# codec_controller.net
KiCad netlist of a schematic drawn in EAGLE
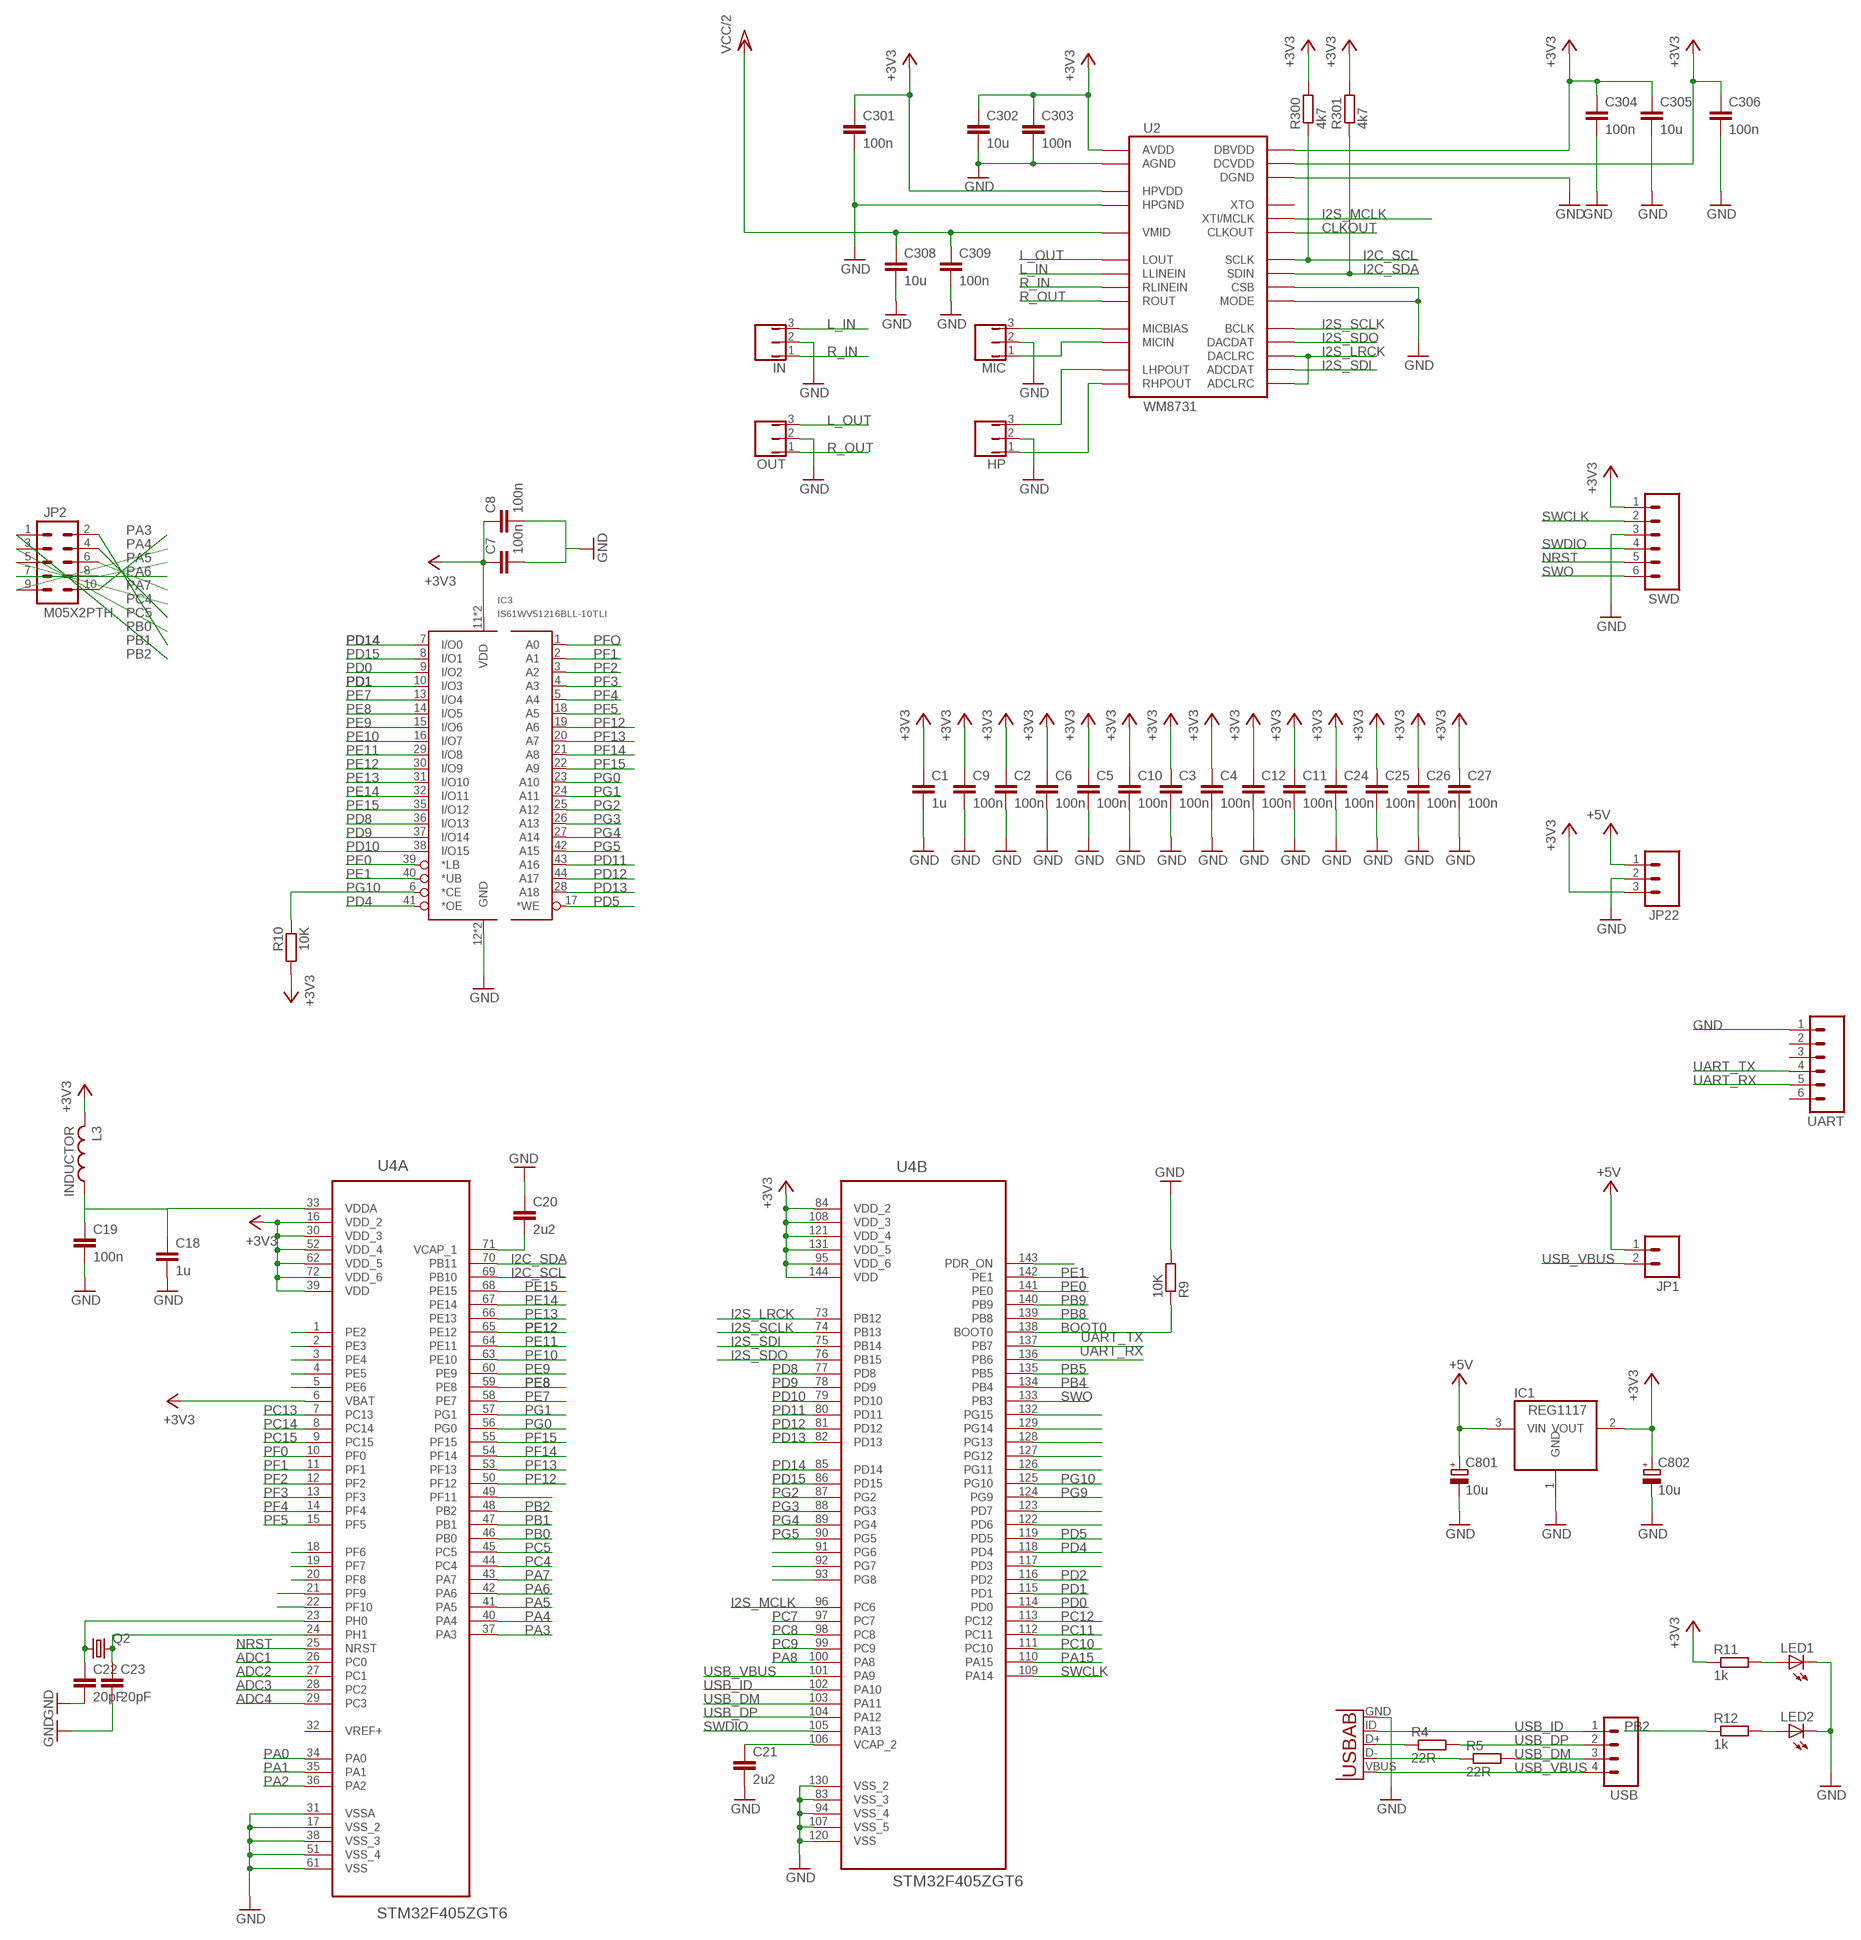
[diagram p0: schematic, sheet 1]

(export (version "E")
  (design (tool "Eeschema 10.0.6"))
  (components
    (comp (ref "C1")
      (value "1u")
      (footprint "eagle-import:C0603")
      (libsource (lib "eagle-import") (part "C-EUC0603"))
    )
    (comp (ref "C2")
      (value "100n")
      (footprint "eagle-import:C0603")
      (libsource (lib "eagle-import") (part "C-EUC0603"))
    )
    (comp (ref "C3")
      (value "100n")
      (footprint "eagle-import:C0603")
      (libsource (lib "eagle-import") (part "C-EUC0603"))
    )
    (comp (ref "C4")
      (value "100n")
      (footprint "eagle-import:C0603")
      (libsource (lib "eagle-import") (part "C-EUC0603"))
    )
    (comp (ref "C5")
      (value "100n")
      (footprint "eagle-import:C0603")
      (libsource (lib "eagle-import") (part "C-EUC0603"))
    )
    (comp (ref "C6")
      (value "100n")
      (footprint "eagle-import:C0603")
      (libsource (lib "eagle-import") (part "C-EUC0603"))
    )
    (comp (ref "C7")
      (value "100n")
      (footprint "eagle-import:C0603")
      (libsource (lib "eagle-import") (part "C-EUC0603"))
    )
    (comp (ref "C8")
      (value "100n")
      (footprint "eagle-import:C0603")
      (libsource (lib "eagle-import") (part "C-EUC0603"))
    )
    (comp (ref "C9")
      (value "100n")
      (footprint "eagle-import:C0603")
      (libsource (lib "eagle-import") (part "C-EUC0603"))
    )
    (comp (ref "C10")
      (value "100n")
      (footprint "eagle-import:C0603")
      (libsource (lib "eagle-import") (part "C-EUC0603"))
    )
    (comp (ref "C11")
      (value "100n")
      (footprint "eagle-import:C0603")
      (libsource (lib "eagle-import") (part "C-EUC0603"))
    )
    (comp (ref "C12")
      (value "100n")
      (footprint "eagle-import:C0603")
      (libsource (lib "eagle-import") (part "C-EUC0603"))
    )
    (comp (ref "C18")
      (value "1u")
      (footprint "eagle-import:C0603")
      (libsource (lib "eagle-import") (part "C-EUC0603"))
    )
    (comp (ref "C19")
      (value "100n")
      (footprint "eagle-import:C0603")
      (libsource (lib "eagle-import") (part "C-EUC0603"))
    )
    (comp (ref "C20")
      (value "2u2")
      (footprint "eagle-import:C0603")
      (libsource (lib "eagle-import") (part "C-EUC0603"))
    )
    (comp (ref "C21")
      (value "2u2")
      (footprint "eagle-import:C0603")
      (libsource (lib "eagle-import") (part "C-EUC0603"))
    )
    (comp (ref "C22")
      (value "20pF")
      (footprint "eagle-import:C0603")
      (libsource (lib "eagle-import") (part "C-EUC0603"))
    )
    (comp (ref "C23")
      (value "20pF")
      (footprint "eagle-import:C0603")
      (libsource (lib "eagle-import") (part "C-EUC0603"))
    )
    (comp (ref "C24")
      (value "100n")
      (footprint "eagle-import:C0603")
      (libsource (lib "eagle-import") (part "C-EUC0603"))
    )
    (comp (ref "C25")
      (value "100n")
      (footprint "eagle-import:C0603")
      (libsource (lib "eagle-import") (part "C-EUC0603"))
    )
    (comp (ref "C26")
      (value "100n")
      (footprint "eagle-import:C0603")
      (libsource (lib "eagle-import") (part "C-EUC0603"))
    )
    (comp (ref "C27")
      (value "100n")
      (footprint "eagle-import:C0603")
      (libsource (lib "eagle-import") (part "C-EUC0603"))
    )
    (comp (ref "C301")
      (value "100n")
      (footprint "eagle-import:C0603")
      (libsource (lib "eagle-import") (part "C-EUC0603"))
    )
    (comp (ref "C302")
      (value "10u")
      (footprint "eagle-import:C1206")
      (libsource (lib "eagle-import") (part "C-EUC1206"))
    )
    (comp (ref "C303")
      (value "100n")
      (footprint "eagle-import:C0603")
      (libsource (lib "eagle-import") (part "C-EUC0603"))
    )
    (comp (ref "C304")
      (value "100n")
      (footprint "eagle-import:C0603")
      (libsource (lib "eagle-import") (part "C-EUC0603"))
    )
    (comp (ref "C305")
      (value "10u")
      (footprint "eagle-import:C1206")
      (libsource (lib "eagle-import") (part "C-EUC1206"))
    )
    (comp (ref "C306")
      (value "100n")
      (footprint "eagle-import:C0603")
      (libsource (lib "eagle-import") (part "C-EUC0603"))
    )
    (comp (ref "C308")
      (value "10u")
      (footprint "eagle-import:C1206")
      (libsource (lib "eagle-import") (part "C-EUC1206"))
    )
    (comp (ref "C309")
      (value "100n")
      (footprint "eagle-import:C0603")
      (libsource (lib "eagle-import") (part "C-EUC0603"))
    )
    (comp (ref "C801")
      (value "10u")
      (footprint "eagle-import:PANASONIC_A")
      (libsource (lib "eagle-import") (part "CPOL-EUA"))
    )
    (comp (ref "C802")
      (value "10u")
      (footprint "eagle-import:PANASONIC_A")
      (libsource (lib "eagle-import") (part "CPOL-EUA"))
    )
    (comp (ref "HP")
      (value "JMP/3P/SIP")
      (footprint "eagle-import:JMP_3P_SIP")
      (libsource (lib "eagle-import") (part "JMP/3P/SIP"))
    )
    (comp (ref "IC1")
      (value "REG1117")
      (footprint "eagle-import:SOT223")
      (libsource (lib "eagle-import") (part "REG1117"))
    )
    (comp (ref "IC3")
      (value "IS61WV51216BLL-10TLI")
      (footprint "eagle-import:TSOP44-II")
      (libsource (lib "eagle-import") (part "IS61WV51216BLL-10TLI"))
    )
    (comp (ref "IN")
      (value "JMP/3P/SIP")
      (footprint "eagle-import:JMP_3P_SIP")
      (libsource (lib "eagle-import") (part "JMP/3P/SIP"))
    )
    (comp (ref "JP1")
      (value "M02PTH")
      (footprint "eagle-import:1X02")
      (libsource (lib "eagle-import") (part "M02PTH"))
    )
    (comp (ref "JP2")
      (value "M05X2PTH")
      (footprint "eagle-import:AVR_ICSP")
      (libsource (lib "eagle-import") (part "M05X2PTH"))
    )
    (comp (ref "JP22")
      (value "M03PTH")
      (footprint "eagle-import:1X03")
      (libsource (lib "eagle-import") (part "M03PTH"))
    )
    (comp (ref "L3")
      (value "INDUCTOR")
      (footprint "eagle-import:0603")
      (libsource (lib "eagle-import") (part "INDUCTOR"))
    )
    (comp (ref "LED1")
      (value "LED1206")
      (footprint "eagle-import:LED-1206")
      (libsource (lib "eagle-import") (part "LED1206"))
    )
    (comp (ref "LED2")
      (value "LED1206")
      (footprint "eagle-import:LED-1206")
      (libsource (lib "eagle-import") (part "LED1206"))
    )
    (comp (ref "MIC")
      (value "JMP/3P/SIP")
      (footprint "eagle-import:JMP_3P_SIP")
      (libsource (lib "eagle-import") (part "JMP/3P/SIP"))
    )
    (comp (ref "OUT")
      (value "JMP/3P/SIP")
      (footprint "eagle-import:JMP_3P_SIP")
      (libsource (lib "eagle-import") (part "JMP/3P/SIP"))
    )
    (comp (ref "Q2")
      (value "CRYSTALHC49UP")
      (footprint "eagle-import:HC49UP")
      (libsource (lib "eagle-import") (part "CRYSTALHC49UP"))
    )
    (comp (ref "R4")
      (value "22R")
      (footprint "eagle-import:R0603")
      (libsource (lib "eagle-import") (part "R-EU_R0603"))
    )
    (comp (ref "R5")
      (value "22R")
      (footprint "eagle-import:R0603")
      (libsource (lib "eagle-import") (part "R-EU_R0603"))
    )
    (comp (ref "R9")
      (value "10K")
      (footprint "eagle-import:R0603")
      (libsource (lib "eagle-import") (part "R-EU_R0603"))
    )
    (comp (ref "R10")
      (value "10K")
      (footprint "eagle-import:R0603")
      (libsource (lib "eagle-import") (part "R-EU_R0603"))
    )
    (comp (ref "R11")
      (value "1k")
      (footprint "eagle-import:R0603")
      (libsource (lib "eagle-import") (part "R-EU_R0603"))
    )
    (comp (ref "R12")
      (value "1k")
      (footprint "eagle-import:R0603")
      (libsource (lib "eagle-import") (part "R-EU_R0603"))
    )
    (comp (ref "R300")
      (value "4k7")
      (footprint "eagle-import:R0603")
      (libsource (lib "eagle-import") (part "R-EU_R0603"))
    )
    (comp (ref "R301")
      (value "4k7")
      (footprint "eagle-import:R0603")
      (libsource (lib "eagle-import") (part "R-EU_R0603"))
    )
    (comp (ref "SWD")
      (value "M06SIP")
      (footprint "eagle-import:1X06")
      (libsource (lib "eagle-import") (part "M06SIP"))
    )
    (comp (ref "U2")
      (value "WM8731")
      (footprint "eagle-import:28-SSOP")
      (libsource (lib "eagle-import") (part "WM8731"))
    )
    (comp (ref "U3")
      (value "USB-AB")
      (footprint "eagle-import:USB-AB-MICRO-SMD")
      (libsource (lib "eagle-import") (part "USB-AB"))
    )
    (comp (ref "U4")
      (value "STM32F405ZGT6")
      (footprint "eagle-import:QFP50P2200X2200X160-144N")
      (libsource (lib "eagle-import") (part "STM32F405ZGT6"))
    )
    (comp (ref "UART")
      (value "M06SIP")
      (footprint "eagle-import:1X06")
      (libsource (lib "eagle-import") (part "M06SIP"))
    )
    (comp (ref "USB")
      (value "M04PTH")
      (footprint "eagle-import:1X04")
      (libsource (lib "eagle-import") (part "M04PTH"))
    )
  )
  (nets
    (net (code "1") (name "+3V3") (class "Default")
      (node (ref "C1") (pin "1") (pinfunction "1_1") (pintype "passive"))
      (node (ref "C10") (pin "1") (pinfunction "1_1") (pintype "passive"))
      (node (ref "C11") (pin "1") (pinfunction "1_1") (pintype "passive"))
      (node (ref "C12") (pin "1") (pinfunction "1_1") (pintype "passive"))
      (node (ref "C2") (pin "1") (pinfunction "1_1") (pintype "passive"))
      (node (ref "C24") (pin "1") (pinfunction "1_1") (pintype "passive"))
      (node (ref "C25") (pin "1") (pinfunction "1_1") (pintype "passive"))
      (node (ref "C26") (pin "1") (pinfunction "1_1") (pintype "passive"))
      (node (ref "C27") (pin "1") (pinfunction "1_1") (pintype "passive"))
      (node (ref "C3") (pin "1") (pinfunction "1_1") (pintype "passive"))
      (node (ref "C301") (pin "1") (pinfunction "1_1") (pintype "passive"))
      (node (ref "C302") (pin "1") (pinfunction "1_1") (pintype "passive"))
      (node (ref "C303") (pin "1") (pinfunction "1_1") (pintype "passive"))
      (node (ref "C304") (pin "1") (pinfunction "1_1") (pintype "passive"))
      (node (ref "C305") (pin "1") (pinfunction "1_1") (pintype "passive"))
      (node (ref "C306") (pin "1") (pinfunction "1_1") (pintype "passive"))
      (node (ref "C4") (pin "1") (pinfunction "1_1") (pintype "passive"))
      (node (ref "C5") (pin "1") (pinfunction "1_1") (pintype "passive"))
      (node (ref "C6") (pin "1") (pinfunction "1_1") (pintype "passive"))
      (node (ref "C7") (pin "1") (pinfunction "1_1") (pintype "passive"))
      (node (ref "C8") (pin "1") (pinfunction "1_1") (pintype "passive"))
      (node (ref "C802") (pin "+") (pinfunction "+_+") (pintype "passive"))
      (node (ref "C9") (pin "1") (pinfunction "1_1") (pintype "passive"))
      (node (ref "IC1") (pin "2") (pinfunction "VOUT_2") (pintype "output"))
      (node (ref "IC3") (pin "11") (pinfunction "VDD_11") (pintype "power_in"))
      (node (ref "IC3") (pin "33") (pinfunction "VDD_33") (pintype "power_in"))
      (node (ref "JP22") (pin "3") (pinfunction "3_3") (pintype "passive"))
      (node (ref "L3") (pin "2") (pinfunction "2_2") (pintype "passive"))
      (node (ref "R10") (pin "2") (pinfunction "2_2") (pintype "passive"))
      (node (ref "R11") (pin "1") (pinfunction "1_1") (pintype "passive"))
      (node (ref "R300") (pin "2") (pinfunction "2_2") (pintype "passive"))
      (node (ref "R301") (pin "2") (pinfunction "2_2") (pintype "passive"))
      (node (ref "SWD") (pin "1") (pinfunction "1_1") (pintype "passive"))
      (node (ref "U2") (pin "P$1") (pinfunction "DBVDD_P$1") (pintype "power_in"))
      (node (ref "U2") (pin "P$14") (pinfunction "AVDD_P$14") (pintype "power_in"))
      (node (ref "U2") (pin "P$27") (pinfunction "DCVDD_P$27") (pintype "power_in"))
      (node (ref "U2") (pin "P$8") (pinfunction "HPVDD_P$8") (pintype "power_in"))
      (node (ref "U4") (pin "108") (pinfunction "VDD_3_108") (pintype "power_in"))
      (node (ref "U4") (pin "121") (pinfunction "VDD_4_121") (pintype "power_in"))
      (node (ref "U4") (pin "131") (pinfunction "VDD_5_131") (pintype "power_in"))
      (node (ref "U4") (pin "144") (pinfunction "VDD_144") (pintype "power_in"))
      (node (ref "U4") (pin "16") (pinfunction "VDD_2_16") (pintype "power_in"))
      (node (ref "U4") (pin "30") (pinfunction "VDD_3_30") (pintype "power_in"))
      (node (ref "U4") (pin "39") (pinfunction "VDD_39") (pintype "power_in"))
      (node (ref "U4") (pin "52") (pinfunction "VDD_4_52") (pintype "power_in"))
      (node (ref "U4") (pin "6") (pinfunction "VBAT_6") (pintype "passive"))
      (node (ref "U4") (pin "62") (pinfunction "VDD_5_62") (pintype "power_in"))
      (node (ref "U4") (pin "72") (pinfunction "VDD_6_72") (pintype "power_in"))
      (node (ref "U4") (pin "84") (pinfunction "VDD_2_84") (pintype "power_in"))
      (node (ref "U4") (pin "95") (pinfunction "VDD_6_95") (pintype "power_in"))
    )
    (net (code "2") (name "+5V") (class "Default")
      (node (ref "C801") (pin "+") (pinfunction "+_+") (pintype "passive"))
      (node (ref "IC1") (pin "3") (pinfunction "VIN_3") (pintype "input"))
      (node (ref "JP1") (pin "1") (pinfunction "1_1") (pintype "passive"))
      (node (ref "JP22") (pin "1") (pinfunction "1_1") (pintype "passive"))
    )
    (net (code "3") (name "/ADC1") (class "Default")
      (node (ref "U4") (pin "26") (pinfunction "PC0_26") (pintype "bidirectional"))
    )
    (net (code "4") (name "/ADC2") (class "Default")
      (node (ref "U4") (pin "27") (pinfunction "PC1_27") (pintype "bidirectional"))
    )
    (net (code "5") (name "/ADC3") (class "Default")
      (node (ref "U4") (pin "28") (pinfunction "PC2_28") (pintype "bidirectional"))
    )
    (net (code "6") (name "/ADC4") (class "Default")
      (node (ref "U4") (pin "29") (pinfunction "PC3_29") (pintype "bidirectional"))
    )
    (net (code "7") (name "/BOOT0") (class "Default")
      (node (ref "R9") (pin "1") (pinfunction "1_1") (pintype "passive"))
      (node (ref "U4") (pin "138") (pinfunction "BOOT0_138") (pintype "passive"))
    )
    (net (code "8") (name "/CLKOUT") (class "Default")
      (node (ref "U2") (pin "P$2") (pinfunction "CLKOUT_P$2") (pintype "output"))
    )
    (net (code "9") (name "/I2C_SCL") (class "Default")
      (node (ref "R300") (pin "1") (pinfunction "1_1") (pintype "passive"))
      (node (ref "U2") (pin "P$24") (pinfunction "SCLK_P$24") (pintype "input"))
      (node (ref "U4") (pin "69") (pinfunction "PB10_69") (pintype "bidirectional"))
    )
    (net (code "10") (name "/I2C_SDA") (class "Default")
      (node (ref "R301") (pin "1") (pinfunction "1_1") (pintype "passive"))
      (node (ref "U2") (pin "P$23") (pinfunction "SDIN_P$23") (pintype "bidirectional"))
      (node (ref "U4") (pin "70") (pinfunction "PB11_70") (pintype "bidirectional"))
    )
    (net (code "11") (name "/I2S_LRCK") (class "Default")
      (node (ref "U2") (pin "P$5") (pinfunction "DACLRC_P$5") (pintype "bidirectional"))
      (node (ref "U2") (pin "P$7") (pinfunction "ADCLRC_P$7") (pintype "bidirectional"))
      (node (ref "U4") (pin "73") (pinfunction "PB12_73") (pintype "bidirectional"))
    )
    (net (code "12") (name "/I2S_MCLK") (class "Default")
      (node (ref "U2") (pin "P$25") (pinfunction "XTI/MCLK_P$25") (pintype "input"))
      (node (ref "U4") (pin "96") (pinfunction "PC6_96") (pintype "bidirectional"))
    )
    (net (code "13") (name "/I2S_SCLK") (class "Default")
      (node (ref "U2") (pin "P$3") (pinfunction "BCLK_P$3") (pintype "bidirectional"))
      (node (ref "U4") (pin "74") (pinfunction "PB13_74") (pintype "bidirectional"))
    )
    (net (code "14") (name "/I2S_SDI") (class "Default")
      (node (ref "U2") (pin "P$6") (pinfunction "ADCDAT_P$6") (pintype "output"))
      (node (ref "U4") (pin "75") (pinfunction "PB14_75") (pintype "bidirectional"))
    )
    (net (code "15") (name "/I2S_SDO") (class "Default")
      (node (ref "U2") (pin "P$4") (pinfunction "DACDAT_P$4") (pintype "input"))
      (node (ref "U4") (pin "76") (pinfunction "PB15_76") (pintype "bidirectional"))
    )
    (net (code "16") (name "/L_IN") (class "Default")
      (node (ref "IN") (pin "3") (pinfunction "3_3") (pintype "passive"))
      (node (ref "U2") (pin "P$20") (pinfunction "LLINEIN_P$20") (pintype "input"))
    )
    (net (code "17") (name "/L_OUT") (class "Default")
      (node (ref "OUT") (pin "3") (pinfunction "3_3") (pintype "passive"))
      (node (ref "U2") (pin "P$12") (pinfunction "LOUT_P$12") (pintype "output"))
    )
    (net (code "18") (name "/NRST") (class "Default")
      (node (ref "SWD") (pin "5") (pinfunction "5_5") (pintype "passive"))
      (node (ref "U4") (pin "25") (pinfunction "NRST_25") (pintype "passive"))
    )
    (net (code "19") (name "/PA0") (class "Default")
      (node (ref "U4") (pin "34") (pinfunction "PA0_34") (pintype "bidirectional"))
    )
    (net (code "20") (name "/PA1") (class "Default")
      (node (ref "U4") (pin "35") (pinfunction "PA1_35") (pintype "bidirectional"))
    )
    (net (code "21") (name "/PA2") (class "Default")
      (node (ref "U4") (pin "36") (pinfunction "PA2_36") (pintype "bidirectional"))
    )
    (net (code "22") (name "/PA3") (class "Default")
      (node (ref "JP2") (pin "10") (pinfunction "10_10") (pintype "passive"))
      (node (ref "U4") (pin "37") (pinfunction "PA3_37") (pintype "bidirectional"))
    )
    (net (code "23") (name "/PA4") (class "Default")
      (node (ref "JP2") (pin "9") (pinfunction "9_9") (pintype "passive"))
      (node (ref "U4") (pin "40") (pinfunction "PA4_40") (pintype "bidirectional"))
    )
    (net (code "24") (name "/PA5") (class "Default")
      (node (ref "JP2") (pin "8") (pinfunction "8_8") (pintype "passive"))
      (node (ref "U4") (pin "41") (pinfunction "PA5_41") (pintype "bidirectional"))
    )
    (net (code "25") (name "/PA6") (class "Default")
      (node (ref "JP2") (pin "7") (pinfunction "7_7") (pintype "passive"))
      (node (ref "U4") (pin "42") (pinfunction "PA6_42") (pintype "bidirectional"))
    )
    (net (code "26") (name "/PA7") (class "Default")
      (node (ref "JP2") (pin "6") (pinfunction "6_6") (pintype "passive"))
      (node (ref "U4") (pin "43") (pinfunction "PA7_43") (pintype "bidirectional"))
    )
    (net (code "27") (name "/PA8") (class "Default")
      (node (ref "U4") (pin "100") (pinfunction "PA8_100") (pintype "bidirectional"))
    )
    (net (code "28") (name "/PA15") (class "Default")
      (node (ref "U4") (pin "110") (pinfunction "PA15_110") (pintype "bidirectional"))
    )
    (net (code "29") (name "/PB0") (class "Default")
      (node (ref "JP2") (pin "3") (pinfunction "3_3") (pintype "passive"))
      (node (ref "U4") (pin "46") (pinfunction "PB0_46") (pintype "bidirectional"))
    )
    (net (code "30") (name "/PB1") (class "Default")
      (node (ref "JP2") (pin "2") (pinfunction "2_2") (pintype "passive"))
      (node (ref "U4") (pin "47") (pinfunction "PB1_47") (pintype "bidirectional"))
    )
    (net (code "31") (name "/PB2") (class "Default")
      (node (ref "JP2") (pin "1") (pinfunction "1_1") (pintype "passive"))
      (node (ref "R12") (pin "1") (pinfunction "1_1") (pintype "passive"))
      (node (ref "U4") (pin "48") (pinfunction "PB2_48") (pintype "bidirectional"))
    )
    (net (code "32") (name "/PB4") (class "Default")
      (node (ref "U4") (pin "134") (pinfunction "PB4_134") (pintype "bidirectional"))
    )
    (net (code "33") (name "/PB5") (class "Default")
      (node (ref "U4") (pin "135") (pinfunction "PB5_135") (pintype "bidirectional"))
    )
    (net (code "34") (name "/PB8") (class "Default")
      (node (ref "U4") (pin "139") (pinfunction "PB8_139") (pintype "bidirectional"))
    )
    (net (code "35") (name "/PB9") (class "Default")
      (node (ref "U4") (pin "140") (pinfunction "PB9_140") (pintype "bidirectional"))
    )
    (net (code "36") (name "/PC4") (class "Default")
      (node (ref "JP2") (pin "5") (pinfunction "5_5") (pintype "passive"))
      (node (ref "U4") (pin "44") (pinfunction "PC4_44") (pintype "bidirectional"))
    )
    (net (code "37") (name "/PC5") (class "Default")
      (node (ref "JP2") (pin "4") (pinfunction "4_4") (pintype "passive"))
      (node (ref "U4") (pin "45") (pinfunction "PC5_45") (pintype "bidirectional"))
    )
    (net (code "38") (name "/PC7") (class "Default")
      (node (ref "U4") (pin "97") (pinfunction "PC7_97") (pintype "bidirectional"))
    )
    (net (code "39") (name "/PC8") (class "Default")
      (node (ref "U4") (pin "98") (pinfunction "PC8_98") (pintype "bidirectional"))
    )
    (net (code "40") (name "/PC9") (class "Default")
      (node (ref "U4") (pin "99") (pinfunction "PC9_99") (pintype "bidirectional"))
    )
    (net (code "41") (name "/PC10") (class "Default")
      (node (ref "U4") (pin "111") (pinfunction "PC10_111") (pintype "bidirectional"))
    )
    (net (code "42") (name "/PC11") (class "Default")
      (node (ref "U4") (pin "112") (pinfunction "PC11_112") (pintype "bidirectional"))
    )
    (net (code "43") (name "/PC12") (class "Default")
      (node (ref "U4") (pin "113") (pinfunction "PC12_113") (pintype "bidirectional"))
    )
    (net (code "44") (name "/PC13") (class "Default")
      (node (ref "U4") (pin "7") (pinfunction "PC13_7") (pintype "bidirectional"))
    )
    (net (code "45") (name "/PC14") (class "Default")
      (node (ref "U4") (pin "8") (pinfunction "PC14_8") (pintype "bidirectional"))
    )
    (net (code "46") (name "/PC15") (class "Default")
      (node (ref "U4") (pin "9") (pinfunction "PC15_9") (pintype "bidirectional"))
    )
    (net (code "47") (name "/PD0") (class "Default")
      (node (ref "IC3") (pin "9") (pinfunction "I/O2_9") (pintype "bidirectional"))
      (node (ref "U4") (pin "114") (pinfunction "PD0_114") (pintype "bidirectional"))
    )
    (net (code "48") (name "/PD1") (class "Default")
      (node (ref "IC3") (pin "10") (pinfunction "I/O3_10") (pintype "bidirectional"))
      (node (ref "U4") (pin "115") (pinfunction "PD1_115") (pintype "bidirectional"))
    )
    (net (code "49") (name "/PD2") (class "Default")
      (node (ref "U4") (pin "116") (pinfunction "PD2_116") (pintype "bidirectional"))
    )
    (net (code "50") (name "/PD4") (class "Default")
      (node (ref "IC3") (pin "41") (pinfunction "*OE_41") (pintype "bidirectional"))
      (node (ref "U4") (pin "118") (pinfunction "PD4_118") (pintype "bidirectional"))
    )
    (net (code "51") (name "/PD5") (class "Default")
      (node (ref "IC3") (pin "17") (pinfunction "*WE_17") (pintype "bidirectional"))
      (node (ref "U4") (pin "119") (pinfunction "PD5_119") (pintype "bidirectional"))
    )
    (net (code "52") (name "/PD8") (class "Default")
      (node (ref "IC3") (pin "36") (pinfunction "I/O13_36") (pintype "bidirectional"))
      (node (ref "U4") (pin "77") (pinfunction "PD8_77") (pintype "bidirectional"))
    )
    (net (code "53") (name "/PD9") (class "Default")
      (node (ref "IC3") (pin "37") (pinfunction "I/O14_37") (pintype "bidirectional"))
      (node (ref "U4") (pin "78") (pinfunction "PD9_78") (pintype "bidirectional"))
    )
    (net (code "54") (name "/PD10") (class "Default")
      (node (ref "IC3") (pin "38") (pinfunction "I/O15_38") (pintype "bidirectional"))
      (node (ref "U4") (pin "79") (pinfunction "PD10_79") (pintype "bidirectional"))
    )
    (net (code "55") (name "/PD11") (class "Default")
      (node (ref "IC3") (pin "43") (pinfunction "A16_43") (pintype "input"))
      (node (ref "U4") (pin "80") (pinfunction "PD11_80") (pintype "bidirectional"))
    )
    (net (code "56") (name "/PD12") (class "Default")
      (node (ref "IC3") (pin "44") (pinfunction "A17_44") (pintype "input"))
      (node (ref "U4") (pin "81") (pinfunction "PD12_81") (pintype "bidirectional"))
    )
    (net (code "57") (name "/PD13") (class "Default")
      (node (ref "IC3") (pin "28") (pinfunction "A18_28") (pintype "input"))
      (node (ref "U4") (pin "82") (pinfunction "PD13_82") (pintype "bidirectional"))
    )
    (net (code "58") (name "/PD14") (class "Default")
      (node (ref "IC3") (pin "7") (pinfunction "I/O0_7") (pintype "bidirectional"))
      (node (ref "U4") (pin "85") (pinfunction "PD14_85") (pintype "bidirectional"))
    )
    (net (code "59") (name "/PD15") (class "Default")
      (node (ref "IC3") (pin "8") (pinfunction "I/O1_8") (pintype "bidirectional"))
      (node (ref "U4") (pin "86") (pinfunction "PD15_86") (pintype "bidirectional"))
    )
    (net (code "60") (name "/PE0") (class "Default")
      (node (ref "IC3") (pin "39") (pinfunction "*LB_39") (pintype "bidirectional"))
      (node (ref "U4") (pin "141") (pinfunction "PE0_141") (pintype "bidirectional"))
    )
    (net (code "61") (name "/PE1") (class "Default")
      (node (ref "IC3") (pin "40") (pinfunction "*UB_40") (pintype "bidirectional"))
      (node (ref "U4") (pin "142") (pinfunction "PE1_142") (pintype "bidirectional"))
    )
    (net (code "62") (name "/PE7") (class "Default")
      (node (ref "IC3") (pin "13") (pinfunction "I/O4_13") (pintype "bidirectional"))
      (node (ref "U4") (pin "58") (pinfunction "PE7_58") (pintype "bidirectional"))
    )
    (net (code "63") (name "/PE8") (class "Default")
      (node (ref "IC3") (pin "14") (pinfunction "I/O5_14") (pintype "bidirectional"))
      (node (ref "U4") (pin "59") (pinfunction "PE8_59") (pintype "bidirectional"))
    )
    (net (code "64") (name "/PE9") (class "Default")
      (node (ref "IC3") (pin "15") (pinfunction "I/O6_15") (pintype "bidirectional"))
      (node (ref "U4") (pin "60") (pinfunction "PE9_60") (pintype "bidirectional"))
    )
    (net (code "65") (name "/PE10") (class "Default")
      (node (ref "IC3") (pin "16") (pinfunction "I/O7_16") (pintype "bidirectional"))
      (node (ref "U4") (pin "63") (pinfunction "PE10_63") (pintype "bidirectional"))
    )
    (net (code "66") (name "/PE11") (class "Default")
      (node (ref "IC3") (pin "29") (pinfunction "I/O8_29") (pintype "bidirectional"))
      (node (ref "U4") (pin "64") (pinfunction "PE11_64") (pintype "bidirectional"))
    )
    (net (code "67") (name "/PE12") (class "Default")
      (node (ref "IC3") (pin "30") (pinfunction "I/O9_30") (pintype "bidirectional"))
      (node (ref "U4") (pin "65") (pinfunction "PE12_65") (pintype "bidirectional"))
    )
    (net (code "68") (name "/PE13") (class "Default")
      (node (ref "IC3") (pin "31") (pinfunction "I/O10_31") (pintype "bidirectional"))
      (node (ref "U4") (pin "66") (pinfunction "PE13_66") (pintype "bidirectional"))
    )
    (net (code "69") (name "/PE14") (class "Default")
      (node (ref "IC3") (pin "32") (pinfunction "I/O11_32") (pintype "bidirectional"))
      (node (ref "U4") (pin "67") (pinfunction "PE14_67") (pintype "bidirectional"))
    )
    (net (code "70") (name "/PE15") (class "Default")
      (node (ref "IC3") (pin "35") (pinfunction "I/O12_35") (pintype "bidirectional"))
      (node (ref "U4") (pin "68") (pinfunction "PE15_68") (pintype "bidirectional"))
    )
    (net (code "71") (name "/PF0") (class "Default")
      (node (ref "U4") (pin "10") (pinfunction "PF0_10") (pintype "bidirectional"))
    )
    (net (code "72") (name "/PF1") (class "Default")
      (node (ref "IC3") (pin "2") (pinfunction "A1_2") (pintype "input"))
      (node (ref "U4") (pin "11") (pinfunction "PF1_11") (pintype "bidirectional"))
    )
    (net (code "73") (name "/PF2") (class "Default")
      (node (ref "IC3") (pin "3") (pinfunction "A2_3") (pintype "input"))
      (node (ref "U4") (pin "12") (pinfunction "PF2_12") (pintype "bidirectional"))
    )
    (net (code "74") (name "/PF3") (class "Default")
      (node (ref "IC3") (pin "4") (pinfunction "A3_4") (pintype "input"))
      (node (ref "U4") (pin "13") (pinfunction "PF3_13") (pintype "bidirectional"))
    )
    (net (code "75") (name "/PF4") (class "Default")
      (node (ref "IC3") (pin "5") (pinfunction "A4_5") (pintype "input"))
      (node (ref "U4") (pin "14") (pinfunction "PF4_14") (pintype "bidirectional"))
    )
    (net (code "76") (name "/PF5") (class "Default")
      (node (ref "IC3") (pin "18") (pinfunction "A5_18") (pintype "input"))
      (node (ref "U4") (pin "15") (pinfunction "PF5_15") (pintype "bidirectional"))
    )
    (net (code "77") (name "/PF12") (class "Default")
      (node (ref "IC3") (pin "19") (pinfunction "A6_19") (pintype "input"))
      (node (ref "U4") (pin "50") (pinfunction "PF12_50") (pintype "bidirectional"))
    )
    (net (code "78") (name "/PF13") (class "Default")
      (node (ref "IC3") (pin "20") (pinfunction "A7_20") (pintype "input"))
      (node (ref "U4") (pin "53") (pinfunction "PF13_53") (pintype "bidirectional"))
    )
    (net (code "79") (name "/PF14") (class "Default")
      (node (ref "IC3") (pin "21") (pinfunction "A8_21") (pintype "input"))
      (node (ref "U4") (pin "54") (pinfunction "PF14_54") (pintype "bidirectional"))
    )
    (net (code "80") (name "/PF15") (class "Default")
      (node (ref "IC3") (pin "22") (pinfunction "A9_22") (pintype "input"))
      (node (ref "U4") (pin "55") (pinfunction "PF15_55") (pintype "bidirectional"))
    )
    (net (code "81") (name "/PFO") (class "Default")
      (node (ref "IC3") (pin "1") (pinfunction "A0_1") (pintype "input"))
    )
    (net (code "82") (name "/PG0") (class "Default")
      (node (ref "IC3") (pin "23") (pinfunction "A10_23") (pintype "input"))
      (node (ref "U4") (pin "56") (pinfunction "PG0_56") (pintype "bidirectional"))
    )
    (net (code "83") (name "/PG1") (class "Default")
      (node (ref "IC3") (pin "24") (pinfunction "A11_24") (pintype "input"))
      (node (ref "U4") (pin "57") (pinfunction "PG1_57") (pintype "bidirectional"))
    )
    (net (code "84") (name "/PG2") (class "Default")
      (node (ref "IC3") (pin "25") (pinfunction "A12_25") (pintype "input"))
      (node (ref "U4") (pin "87") (pinfunction "PG2_87") (pintype "bidirectional"))
    )
    (net (code "85") (name "/PG3") (class "Default")
      (node (ref "IC3") (pin "26") (pinfunction "A13_26") (pintype "input"))
      (node (ref "U4") (pin "88") (pinfunction "PG3_88") (pintype "bidirectional"))
    )
    (net (code "86") (name "/PG4") (class "Default")
      (node (ref "IC3") (pin "27") (pinfunction "A14_27") (pintype "input"))
      (node (ref "U4") (pin "89") (pinfunction "PG4_89") (pintype "bidirectional"))
    )
    (net (code "87") (name "/PG5") (class "Default")
      (node (ref "IC3") (pin "42") (pinfunction "A15_42") (pintype "input"))
      (node (ref "U4") (pin "90") (pinfunction "PG5_90") (pintype "bidirectional"))
    )
    (net (code "88") (name "/PG9") (class "Default")
      (node (ref "U4") (pin "124") (pinfunction "PG9_124") (pintype "bidirectional"))
    )
    (net (code "89") (name "/PG10") (class "Default")
      (node (ref "IC3") (pin "6") (pinfunction "*CE_6") (pintype "bidirectional"))
      (node (ref "R10") (pin "1") (pinfunction "1_1") (pintype "passive"))
      (node (ref "U4") (pin "125") (pinfunction "PG10_125") (pintype "bidirectional"))
    )
    (net (code "90") (name "/R_IN") (class "Default")
      (node (ref "IN") (pin "1") (pinfunction "1_1") (pintype "passive"))
      (node (ref "U2") (pin "P$19") (pinfunction "RLINEIN_P$19") (pintype "input"))
    )
    (net (code "91") (name "/R_OUT") (class "Default")
      (node (ref "OUT") (pin "1") (pinfunction "1_1") (pintype "passive"))
      (node (ref "U2") (pin "P$13") (pinfunction "ROUT_P$13") (pintype "output"))
    )
    (net (code "92") (name "/SWCLK") (class "Default")
      (node (ref "SWD") (pin "2") (pinfunction "2_2") (pintype "passive"))
      (node (ref "U4") (pin "109") (pinfunction "PA14_109") (pintype "bidirectional"))
    )
    (net (code "93") (name "/SWDIO") (class "Default")
      (node (ref "SWD") (pin "4") (pinfunction "4_4") (pintype "passive"))
      (node (ref "U4") (pin "105") (pinfunction "PA13_105") (pintype "bidirectional"))
    )
    (net (code "94") (name "/SWO") (class "Default")
      (node (ref "SWD") (pin "6") (pinfunction "6_6") (pintype "passive"))
      (node (ref "U4") (pin "133") (pinfunction "PB3_133") (pintype "bidirectional"))
    )
    (net (code "95") (name "/UART_RX") (class "Default")
      (node (ref "U4") (pin "136") (pinfunction "PB6_136") (pintype "bidirectional"))
      (node (ref "UART") (pin "5") (pinfunction "5_5") (pintype "passive"))
    )
    (net (code "96") (name "/UART_TX") (class "Default")
      (node (ref "U4") (pin "137") (pinfunction "PB7_137") (pintype "bidirectional"))
      (node (ref "UART") (pin "4") (pinfunction "4_4") (pintype "passive"))
    )
    (net (code "97") (name "/USB_DM") (class "Default")
      (node (ref "R5") (pin "2") (pinfunction "2_2") (pintype "passive"))
      (node (ref "U4") (pin "103") (pinfunction "PA11_103") (pintype "bidirectional"))
      (node (ref "USB") (pin "3") (pinfunction "3_3") (pintype "passive"))
    )
    (net (code "98") (name "/USB_DP") (class "Default")
      (node (ref "R4") (pin "2") (pinfunction "2_2") (pintype "passive"))
      (node (ref "U4") (pin "104") (pinfunction "PA12_104") (pintype "bidirectional"))
      (node (ref "USB") (pin "2") (pinfunction "2_2") (pintype "passive"))
    )
    (net (code "99") (name "/USB_ID") (class "Default")
      (node (ref "U3") (pin "ID") (pinfunction "USBID_ID") (pintype "bidirectional"))
      (node (ref "U4") (pin "102") (pinfunction "PA10_102") (pintype "bidirectional"))
      (node (ref "USB") (pin "1") (pinfunction "1_1") (pintype "passive"))
    )
    (net (code "100") (name "/USB_VBUS") (class "Default")
      (node (ref "JP1") (pin "2") (pinfunction "2_2") (pintype "passive"))
      (node (ref "U3") (pin "VBUS") (pinfunction "VBUS_VBUS") (pintype "bidirectional"))
      (node (ref "U4") (pin "101") (pinfunction "PA9_101") (pintype "bidirectional"))
      (node (ref "USB") (pin "4") (pinfunction "4_4") (pintype "passive"))
    )
    (net (code "101") (name "GND") (class "Default")
      (node (ref "C1") (pin "2") (pinfunction "2_2") (pintype "passive"))
      (node (ref "C10") (pin "2") (pinfunction "2_2") (pintype "passive"))
      (node (ref "C11") (pin "2") (pinfunction "2_2") (pintype "passive"))
      (node (ref "C12") (pin "2") (pinfunction "2_2") (pintype "passive"))
      (node (ref "C18") (pin "2") (pinfunction "2_2") (pintype "passive"))
      (node (ref "C19") (pin "2") (pinfunction "2_2") (pintype "passive"))
      (node (ref "C2") (pin "2") (pinfunction "2_2") (pintype "passive"))
      (node (ref "C20") (pin "1") (pinfunction "1_1") (pintype "passive"))
      (node (ref "C21") (pin "2") (pinfunction "2_2") (pintype "passive"))
      (node (ref "C22") (pin "2") (pinfunction "2_2") (pintype "passive"))
      (node (ref "C23") (pin "2") (pinfunction "2_2") (pintype "passive"))
      (node (ref "C24") (pin "2") (pinfunction "2_2") (pintype "passive"))
      (node (ref "C25") (pin "2") (pinfunction "2_2") (pintype "passive"))
      (node (ref "C26") (pin "2") (pinfunction "2_2") (pintype "passive"))
      (node (ref "C27") (pin "2") (pinfunction "2_2") (pintype "passive"))
      (node (ref "C3") (pin "2") (pinfunction "2_2") (pintype "passive"))
      (node (ref "C301") (pin "2") (pinfunction "2_2") (pintype "passive"))
      (node (ref "C302") (pin "2") (pinfunction "2_2") (pintype "passive"))
      (node (ref "C303") (pin "2") (pinfunction "2_2") (pintype "passive"))
      (node (ref "C304") (pin "2") (pinfunction "2_2") (pintype "passive"))
      (node (ref "C305") (pin "2") (pinfunction "2_2") (pintype "passive"))
      (node (ref "C306") (pin "2") (pinfunction "2_2") (pintype "passive"))
      (node (ref "C308") (pin "2") (pinfunction "2_2") (pintype "passive"))
      (node (ref "C309") (pin "2") (pinfunction "2_2") (pintype "passive"))
      (node (ref "C4") (pin "2") (pinfunction "2_2") (pintype "passive"))
      (node (ref "C5") (pin "2") (pinfunction "2_2") (pintype "passive"))
      (node (ref "C6") (pin "2") (pinfunction "2_2") (pintype "passive"))
      (node (ref "C7") (pin "2") (pinfunction "2_2") (pintype "passive"))
      (node (ref "C8") (pin "2") (pinfunction "2_2") (pintype "passive"))
      (node (ref "C801") (pin "-") (pinfunction "-_-") (pintype "passive"))
      (node (ref "C802") (pin "-") (pinfunction "-_-") (pintype "passive"))
      (node (ref "C9") (pin "2") (pinfunction "2_2") (pintype "passive"))
      (node (ref "HP") (pin "2") (pinfunction "2_2") (pintype "passive"))
      (node (ref "IC1") (pin "1") (pinfunction "GND_1") (pintype "power_in"))
      (node (ref "IC3") (pin "12") (pinfunction "GND_12") (pintype "power_in"))
      (node (ref "IC3") (pin "34") (pinfunction "GND_34") (pintype "power_in"))
      (node (ref "IN") (pin "2") (pinfunction "2_2") (pintype "passive"))
      (node (ref "JP22") (pin "2") (pinfunction "2_2") (pintype "passive"))
      (node (ref "LED1") (pin "C") (pinfunction "C_C") (pintype "passive"))
      (node (ref "LED2") (pin "C") (pinfunction "C_C") (pintype "passive"))
      (node (ref "MIC") (pin "2") (pinfunction "2_2") (pintype "passive"))
      (node (ref "OUT") (pin "2") (pinfunction "2_2") (pintype "passive"))
      (node (ref "R9") (pin "2") (pinfunction "2_2") (pintype "passive"))
      (node (ref "SWD") (pin "3") (pinfunction "3_3") (pintype "passive"))
      (node (ref "U2") (pin "P$11") (pinfunction "HPGND_P$11") (pintype "power_in"))
      (node (ref "U2") (pin "P$15") (pinfunction "AGND_P$15") (pintype "power_in"))
      (node (ref "U2") (pin "P$21") (pinfunction "MODE_P$21") (pintype "input"))
      (node (ref "U2") (pin "P$22") (pinfunction "CSB_P$22") (pintype "input"))
      (node (ref "U2") (pin "P$28") (pinfunction "DGND_P$28") (pintype "power_in"))
      (node (ref "U3") (pin "GND") (pinfunction "GND_GND") (pintype "bidirectional"))
      (node (ref "U4") (pin "107") (pinfunction "VSS_5_107") (pintype "power_in"))
      (node (ref "U4") (pin "120") (pinfunction "VSS_120") (pintype "power_in"))
      (node (ref "U4") (pin "130") (pinfunction "VSS_2_130") (pintype "power_in"))
      (node (ref "U4") (pin "17") (pinfunction "VSS_2_17") (pintype "power_in"))
      (node (ref "U4") (pin "31") (pinfunction "VSSA_31") (pintype "power_in"))
      (node (ref "U4") (pin "38") (pinfunction "VSS_3_38") (pintype "power_in"))
      (node (ref "U4") (pin "51") (pinfunction "VSS_4_51") (pintype "power_in"))
      (node (ref "U4") (pin "61") (pinfunction "VSS_61") (pintype "power_in"))
      (node (ref "U4") (pin "83") (pinfunction "VSS_3_83") (pintype "power_in"))
      (node (ref "U4") (pin "94") (pinfunction "VSS_4_94") (pintype "power_in"))
      (node (ref "UART") (pin "1") (pinfunction "1_1") (pintype "passive"))
    )
    (net (code "102") (name "Net-(LED1-PadA)") (class "Default")
      (node (ref "LED1") (pin "A") (pinfunction "A_A") (pintype "passive"))
      (node (ref "R11") (pin "2") (pinfunction "2_2") (pintype "passive"))
    )
    (net (code "103") (name "Net-(LED2-PadA)") (class "Default")
      (node (ref "LED2") (pin "A") (pinfunction "A_A") (pintype "passive"))
      (node (ref "R12") (pin "2") (pinfunction "2_2") (pintype "passive"))
    )
    (net (code "104") (name "Net-(R4-Pad1)") (class "Default")
      (node (ref "R4") (pin "1") (pinfunction "1_1") (pintype "passive"))
      (node (ref "U3") (pin "D+") (pinfunction "D+_D+") (pintype "bidirectional"))
    )
    (net (code "105") (name "Net-(R5-Pad1)") (class "Default")
      (node (ref "R5") (pin "1") (pinfunction "1_1") (pintype "passive"))
      (node (ref "U3") (pin "D-") (pinfunction "D-_D-") (pintype "bidirectional"))
    )
    (net (code "106") (name "Net-(U2-LHPOUT)") (class "Default")
      (node (ref "HP") (pin "3") (pinfunction "3_3") (pintype "passive"))
      (node (ref "U2") (pin "P$9") (pinfunction "LHPOUT_P$9") (pintype "output"))
    )
    (net (code "107") (name "Net-(U2-MICBIAS)") (class "Default")
      (node (ref "MIC") (pin "3") (pinfunction "3_3") (pintype "passive"))
      (node (ref "U2") (pin "P$17") (pinfunction "MICBIAS_P$17") (pintype "output"))
    )
    (net (code "108") (name "Net-(U2-MICIN)") (class "Default")
      (node (ref "MIC") (pin "1") (pinfunction "1_1") (pintype "passive"))
      (node (ref "U2") (pin "P$18") (pinfunction "MICIN_P$18") (pintype "input"))
    )
    (net (code "109") (name "Net-(U2-RHPOUT)") (class "Default")
      (node (ref "HP") (pin "1") (pinfunction "1_1") (pintype "passive"))
      (node (ref "U2") (pin "P$10") (pinfunction "RHPOUT_P$10") (pintype "output"))
    )
    (net (code "110") (name "Net-(U4A-PH0)") (class "Default")
      (node (ref "C22") (pin "1") (pinfunction "1_1") (pintype "passive"))
      (node (ref "Q2") (pin "1") (pinfunction "1_1") (pintype "passive"))
      (node (ref "U4") (pin "23") (pinfunction "PH0_23") (pintype "bidirectional"))
    )
    (net (code "111") (name "Net-(U4A-PH1)") (class "Default")
      (node (ref "C23") (pin "1") (pinfunction "1_1") (pintype "passive"))
      (node (ref "Q2") (pin "2") (pinfunction "2_2") (pintype "passive"))
      (node (ref "U4") (pin "24") (pinfunction "PH1_24") (pintype "bidirectional"))
    )
    (net (code "112") (name "Net-(U4A-VCAP_1)") (class "Default")
      (node (ref "C20") (pin "2") (pinfunction "2_2") (pintype "passive"))
      (node (ref "U4") (pin "71") (pinfunction "VCAP_1_71") (pintype "passive"))
    )
    (net (code "113") (name "Net-(U4A-VDDA)") (class "Default")
      (node (ref "C18") (pin "1") (pinfunction "1_1") (pintype "passive"))
      (node (ref "C19") (pin "1") (pinfunction "1_1") (pintype "passive"))
      (node (ref "L3") (pin "1") (pinfunction "1_1") (pintype "passive"))
      (node (ref "U4") (pin "33") (pinfunction "VDDA_33") (pintype "power_in"))
    )
    (net (code "114") (name "Net-(U4B-VCAP_2)") (class "Default")
      (node (ref "C21") (pin "1") (pinfunction "1_1") (pintype "passive"))
      (node (ref "U4") (pin "106") (pinfunction "VCAP_2_106") (pintype "passive"))
    )
    (net (code "115") (name "VCC{slash}2") (class "Default")
      (node (ref "C308") (pin "1") (pinfunction "1_1") (pintype "passive"))
      (node (ref "C309") (pin "1") (pinfunction "1_1") (pintype "passive"))
      (node (ref "U2") (pin "P$16") (pinfunction "VMID_P$16") (pintype "output"))
    )
    (net (code "116") (name "unconnected-(U2-XTO-PadP$26)") (class "Default")
      (node (ref "U2") (pin "P$26") (pinfunction "XTO_P$26") (pintype "output"))
    )
    (net (code "117") (name "unconnected-(U4A-PE2-Pad1)") (class "Default")
      (node (ref "U4") (pin "1") (pinfunction "PE2_1") (pintype "bidirectional"))
    )
    (net (code "118") (name "unconnected-(U4A-PE3-Pad2)") (class "Default")
      (node (ref "U4") (pin "2") (pinfunction "PE3_2") (pintype "bidirectional"))
    )
    (net (code "119") (name "unconnected-(U4A-PE4-Pad3)") (class "Default")
      (node (ref "U4") (pin "3") (pinfunction "PE4_3") (pintype "bidirectional"))
    )
    (net (code "120") (name "unconnected-(U4A-PE5-Pad4)") (class "Default")
      (node (ref "U4") (pin "4") (pinfunction "PE5_4") (pintype "bidirectional"))
    )
    (net (code "121") (name "unconnected-(U4A-PE6-Pad5)") (class "Default")
      (node (ref "U4") (pin "5") (pinfunction "PE6_5") (pintype "bidirectional"))
    )
    (net (code "122") (name "unconnected-(U4A-PF6-Pad18)") (class "Default")
      (node (ref "U4") (pin "18") (pinfunction "PF6_18") (pintype "bidirectional"))
    )
    (net (code "123") (name "unconnected-(U4A-PF7-Pad19)") (class "Default")
      (node (ref "U4") (pin "19") (pinfunction "PF7_19") (pintype "bidirectional"))
    )
    (net (code "124") (name "unconnected-(U4A-PF8-Pad20)") (class "Default")
      (node (ref "U4") (pin "20") (pinfunction "PF8_20") (pintype "bidirectional"))
    )
    (net (code "125") (name "unconnected-(U4A-PF9-Pad21)") (class "Default")
      (node (ref "U4") (pin "21") (pinfunction "PF9_21") (pintype "bidirectional"))
    )
    (net (code "126") (name "unconnected-(U4A-PF10-Pad22)") (class "Default")
      (node (ref "U4") (pin "22") (pinfunction "PF10_22") (pintype "bidirectional"))
    )
    (net (code "127") (name "unconnected-(U4A-PF11-Pad49)") (class "Default")
      (node (ref "U4") (pin "49") (pinfunction "PF11_49") (pintype "bidirectional"))
    )
    (net (code "128") (name "unconnected-(U4A-VREF+-Pad32)") (class "Default")
      (node (ref "U4") (pin "32") (pinfunction "VREF+_32") (pintype "passive"))
    )
    (net (code "129") (name "unconnected-(U4B-PD3-Pad117)") (class "Default")
      (node (ref "U4") (pin "117") (pinfunction "PD3_117") (pintype "bidirectional"))
    )
    (net (code "130") (name "unconnected-(U4B-PD6-Pad122)") (class "Default")
      (node (ref "U4") (pin "122") (pinfunction "PD6_122") (pintype "bidirectional"))
    )
    (net (code "131") (name "unconnected-(U4B-PD7-Pad123)") (class "Default")
      (node (ref "U4") (pin "123") (pinfunction "PD7_123") (pintype "bidirectional"))
    )
    (net (code "132") (name "unconnected-(U4B-PDR_ON-Pad143)") (class "Default")
      (node (ref "U4") (pin "143") (pinfunction "PDR_ON_143") (pintype "passive"))
    )
    (net (code "133") (name "unconnected-(U4B-PG6-Pad91)") (class "Default")
      (node (ref "U4") (pin "91") (pinfunction "PG6_91") (pintype "bidirectional"))
    )
    (net (code "134") (name "unconnected-(U4B-PG7-Pad92)") (class "Default")
      (node (ref "U4") (pin "92") (pinfunction "PG7_92") (pintype "bidirectional"))
    )
    (net (code "135") (name "unconnected-(U4B-PG8-Pad93)") (class "Default")
      (node (ref "U4") (pin "93") (pinfunction "PG8_93") (pintype "bidirectional"))
    )
    (net (code "136") (name "unconnected-(U4B-PG11-Pad126)") (class "Default")
      (node (ref "U4") (pin "126") (pinfunction "PG11_126") (pintype "bidirectional"))
    )
    (net (code "137") (name "unconnected-(U4B-PG12-Pad127)") (class "Default")
      (node (ref "U4") (pin "127") (pinfunction "PG12_127") (pintype "bidirectional"))
    )
    (net (code "138") (name "unconnected-(U4B-PG13-Pad128)") (class "Default")
      (node (ref "U4") (pin "128") (pinfunction "PG13_128") (pintype "bidirectional"))
    )
    (net (code "139") (name "unconnected-(U4B-PG14-Pad129)") (class "Default")
      (node (ref "U4") (pin "129") (pinfunction "PG14_129") (pintype "bidirectional"))
    )
    (net (code "140") (name "unconnected-(U4B-PG15-Pad132)") (class "Default")
      (node (ref "U4") (pin "132") (pinfunction "PG15_132") (pintype "bidirectional"))
    )
    (net (code "141") (name "unconnected-(UART-Pad2)") (class "Default")
      (node (ref "UART") (pin "2") (pinfunction "2_2") (pintype "passive"))
    )
    (net (code "142") (name "unconnected-(UART-Pad3)") (class "Default")
      (node (ref "UART") (pin "3") (pinfunction "3_3") (pintype "passive"))
    )
    (net (code "143") (name "unconnected-(UART-Pad6)") (class "Default")
      (node (ref "UART") (pin "6") (pinfunction "6_6") (pintype "passive"))
    )
  )
)
